# power.net
KiCad netlist of a schematic drawn in Altium Designer
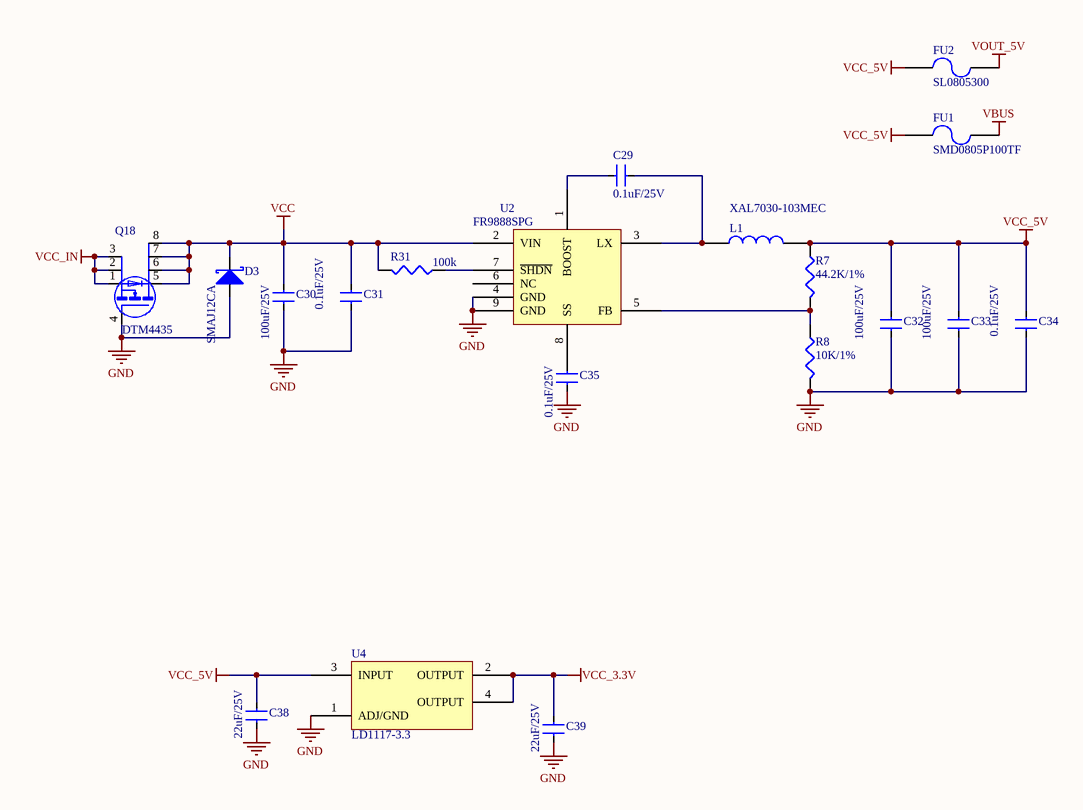
[diagram p0: power.SchDoc]

(export (version "E")
  (design (tool "Eeschema 10.0.6"))
  (components
    (comp (ref "C29")
      (value "0.1uF/25V")
      (footprint "0603C")
      (description "CCX85-103")
      (libsource (lib "无极性电容") (part "0.01UF"))
    )
    (comp (ref "C30")
      (value "100uF/25V")
      (footprint "1210C")
      (description "CCX85-103")
      (libsource (lib "无极性电容") (part "0.01UF"))
    )
    (comp (ref "C31")
      (value "0.1uF/25V")
      (footprint "0603C")
      (description "CCX85-103")
      (libsource (lib "无极性电容") (part "0.01UF"))
    )
    (comp (ref "C32")
      (value "100uF/25V")
      (footprint "1210C")
      (description "CCX85-103")
      (libsource (lib "无极性电容") (part "0.01UF"))
    )
    (comp (ref "C33")
      (value "100uF/25V")
      (footprint "1210C")
      (description "CCX85-103")
      (libsource (lib "无极性电容") (part "0.01UF"))
    )
    (comp (ref "C34")
      (value "0.1uF/25V")
      (footprint "0603C")
      (description "CCX85-103")
      (libsource (lib "无极性电容") (part "0.01UF"))
    )
    (comp (ref "C35")
      (value "0.1uF/25V")
      (footprint "0603C")
      (description "CCX85-103")
      (libsource (lib "无极性电容") (part "0.01UF"))
    )
    (comp (ref "C38")
      (value "22uF/25V")
      (footprint "1210C")
      (description "CCX85-103")
      (libsource (lib "无极性电容") (part "0.01UF"))
    )
    (comp (ref "C39")
      (value "22uF/25V")
      (footprint "1210C")
      (description "CCX85-103")
      (libsource (lib "无极性电容") (part "0.01UF"))
    )
    (comp (ref "D3")
      (value "SMAJ12CA")
      (footprint "SMA")
      (description "Schottky Diode")
      (libsource (lib "*") (part "DIODE S"))
    )
    (comp (ref "FU1")
      (value "SMD0805P100TF")
      (footprint "F0805")
      (description "Fuse")
      (libsource (lib "SM") (part "FUSE2"))
    )
    (comp (ref "FU2")
      (value "SL0805300")
      (footprint "F0805")
      (description "Fuse")
      (libsource (lib "SM") (part "FUSE2"))
    )
    (comp (ref "L1") (value "XAL7030-103MEC") (footprint "XAL7030") (libsource (lib "*") (part "INDUCTOR")))
    (comp (ref "Q18")
      (value "DTM4435")
      (footprint "SO-8")
      (description "Si4004DY")
      (libsource (lib "Schlib_20110825") (part "Si4004DY"))
    )
    (comp (ref "R7")
      (value "44.2K/1%")
      (footprint "0603R")
      (description "Resistor")
      (fields (field (name "PUBLISHER") "Altium Limited"))
      (libsource (lib "SM") (part "Res3"))
    )
    (comp (ref "R8")
      (value "10K/1%")
      (footprint "0603R")
      (description "Resistor")
      (fields (field (name "PUBLISHER") "Altium Limited"))
      (libsource (lib "SM") (part "Res3"))
    )
    (comp (ref "R31")
      (value "100k")
      (footprint "0603R")
      (description "Resistor")
      (fields (field (name "PUBLISHER") "Altium Limited"))
      (libsource (lib "SM") (part "Res3"))
    )
    (comp (ref "U2")
      (value "FR9888SPG")
      (footprint "SOP120P600-8N")
      (libsource (lib "stm32") (part "FR9888SPG"))
    )
    (comp (ref "U4") (value "LD1117-3.3") (footprint "sot223") (libsource (lib "stm32") (part "LD1117-1.2")))
  )
  (nets
    (net (code "1") (name "GND") (class "Default")
      (node (ref "C30") (pin "2") (pinfunction "2_2") (pintype "passive"))
      (node (ref "C31") (pin "2") (pinfunction "2_2") (pintype "passive"))
      (node (ref "C32") (pin "2") (pinfunction "2_2") (pintype "passive"))
      (node (ref "C33") (pin "2") (pinfunction "2_2") (pintype "passive"))
      (node (ref "C34") (pin "2") (pinfunction "2_2") (pintype "passive"))
      (node (ref "C35") (pin "2") (pinfunction "2_2") (pintype "passive"))
      (node (ref "C38") (pin "2") (pinfunction "2_2") (pintype "passive"))
      (node (ref "C39") (pin "2") (pinfunction "2_2") (pintype "passive"))
      (node (ref "D3") (pin "1") (pinfunction "A_1") (pintype "passive"))
      (node (ref "Q18") (pin "4") (pinfunction "G_4") (pintype "passive"))
      (node (ref "R8") (pin "2") (pinfunction "2_2") (pintype "passive"))
      (node (ref "U2") (pin "4") (pinfunction "GND_4") (pintype "passive"))
      (node (ref "U2") (pin "9") (pinfunction "GND_9") (pintype "passive"))
      (node (ref "U4") (pin "1") (pinfunction "ADJ/GND_1") (pintype "passive"))
    )
    (net (code "2") (name "Net-(U2-BOOST)") (class "Default")
      (node (ref "C29") (pin "1") (pinfunction "1_1") (pintype "passive"))
      (node (ref "U2") (pin "1") (pinfunction "BOOST_1") (pintype "passive"))
    )
    (net (code "3") (name "Net-(U2-FB)") (class "Default")
      (node (ref "R7") (pin "2") (pinfunction "2_2") (pintype "passive"))
      (node (ref "R8") (pin "1") (pinfunction "1_1") (pintype "passive"))
      (node (ref "U2") (pin "5") (pinfunction "FB_5") (pintype "passive"))
    )
    (net (code "4") (name "Net-(U2-LX)") (class "Default")
      (node (ref "C29") (pin "2") (pinfunction "2_2") (pintype "passive"))
      (node (ref "L1") (pin "1") (pinfunction "1_1") (pintype "passive"))
      (node (ref "U2") (pin "3") (pinfunction "LX_3") (pintype "passive"))
    )
    (net (code "5") (name "Net-(U2-SS)") (class "Default")
      (node (ref "C35") (pin "1") (pinfunction "1_1") (pintype "passive"))
      (node (ref "U2") (pin "8") (pinfunction "SS_8") (pintype "passive"))
    )
    (net (code "6") (name "Net-(U2-~{SHDN})") (class "Default")
      (node (ref "R31") (pin "1") (pinfunction "1_1") (pintype "passive"))
      (node (ref "U2") (pin "7") (pinfunction "~{SHDN}_7") (pintype "passive"))
    )
    (net (code "7") (name "VBUS") (class "Default")
      (node (ref "FU1") (pin "2") (pinfunction "2_2") (pintype "passive"))
    )
    (net (code "8") (name "VCC") (class "Default")
      (node (ref "C30") (pin "1") (pinfunction "1_1") (pintype "passive"))
      (node (ref "C31") (pin "1") (pinfunction "1_1") (pintype "passive"))
      (node (ref "D3") (pin "2") (pinfunction "K_2") (pintype "passive"))
      (node (ref "Q18") (pin "5") (pinfunction "D_5") (pintype "passive"))
      (node (ref "Q18") (pin "6") (pinfunction "D_6") (pintype "passive"))
      (node (ref "Q18") (pin "7") (pinfunction "D_7") (pintype "passive"))
      (node (ref "Q18") (pin "8") (pinfunction "D_8") (pintype "passive"))
      (node (ref "R31") (pin "2") (pinfunction "2_2") (pintype "passive"))
      (node (ref "U2") (pin "2") (pinfunction "VIN_2") (pintype "passive"))
    )
    (net (code "9") (name "VCC_3.3V") (class "Default")
      (node (ref "C39") (pin "1") (pinfunction "1_1") (pintype "passive"))
      (node (ref "U4") (pin "2") (pinfunction "OUTPUT_2") (pintype "passive"))
      (node (ref "U4") (pin "4") (pinfunction "OUTPUT_4") (pintype "passive"))
    )
    (net (code "10") (name "VCC_5V") (class "Default")
      (node (ref "C32") (pin "1") (pinfunction "1_1") (pintype "passive"))
      (node (ref "C33") (pin "1") (pinfunction "1_1") (pintype "passive"))
      (node (ref "C34") (pin "1") (pinfunction "1_1") (pintype "passive"))
      (node (ref "C38") (pin "1") (pinfunction "1_1") (pintype "passive"))
      (node (ref "FU1") (pin "1") (pinfunction "1_1") (pintype "passive"))
      (node (ref "FU2") (pin "1") (pinfunction "1_1") (pintype "passive"))
      (node (ref "L1") (pin "2") (pinfunction "2_2") (pintype "passive"))
      (node (ref "R7") (pin "1") (pinfunction "1_1") (pintype "passive"))
      (node (ref "U4") (pin "3") (pinfunction "INPUT_3") (pintype "passive"))
    )
    (net (code "11") (name "VCC_IN") (class "Default")
      (node (ref "Q18") (pin "1") (pinfunction "S_1") (pintype "passive"))
      (node (ref "Q18") (pin "2") (pinfunction "S_2") (pintype "passive"))
      (node (ref "Q18") (pin "3") (pinfunction "S_3") (pintype "passive"))
    )
    (net (code "12") (name "VOUT_5V") (class "Default")
      (node (ref "FU2") (pin "2") (pinfunction "2_2") (pintype "passive"))
    )
    (net (code "13") (name "unconnected-(U2-NC-Pad6)") (class "Default")
      (node (ref "U2") (pin "6") (pinfunction "NC_6") (pintype "passive"))
    )
  )
)
